# SerialLvlConvert.net
KiCad netlist of a schematic drawn in Altium Designer
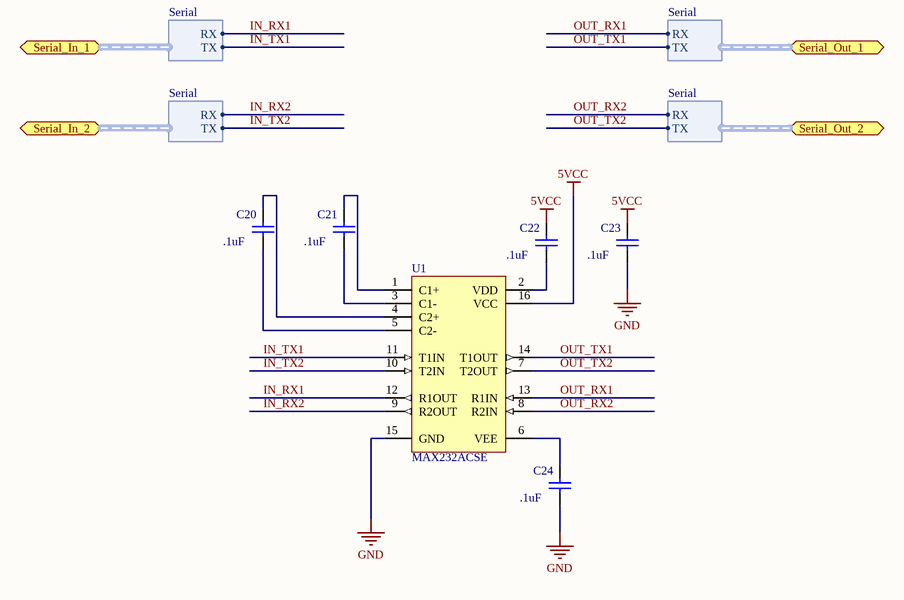
[diagram p0: SerialLvlConvert.SchDoc]

(export (version "E")
  (design (tool "Eeschema 10.0.6"))
  (components
    (comp (ref "C20")
      (value ".1uF")
      (footprint "0402")
      (description "Capacitor (Semiconductor SIM Model)")
      (fields (field (name "Comment") "Cap Semi") (field (name "PUBLISHER") "Altium Limited"))
      (libsource (lib "Miscellaneous Devices") (part "Cap Semi"))
    )
    (comp (ref "C21")
      (value ".1uF")
      (footprint "0402")
      (description "Capacitor (Semiconductor SIM Model)")
      (fields (field (name "Comment") "Cap Semi") (field (name "PUBLISHER") "Altium Limited"))
      (libsource (lib "Miscellaneous Devices") (part "Cap Semi"))
    )
    (comp (ref "C22")
      (value ".1uF")
      (footprint "0402")
      (description "Capacitor (Semiconductor SIM Model)")
      (fields (field (name "Comment") "Cap Semi") (field (name "PUBLISHER") "Altium Limited"))
      (libsource (lib "Miscellaneous Devices") (part "Cap Semi"))
    )
    (comp (ref "C23")
      (value ".1uF")
      (footprint "0402")
      (description "Capacitor (Semiconductor SIM Model)")
      (fields (field (name "Comment") "Cap Semi") (field (name "PUBLISHER") "Altium Limited"))
      (libsource (lib "Miscellaneous Devices") (part "Cap Semi"))
    )
    (comp (ref "C24")
      (value ".1uF")
      (footprint "0402")
      (description "Capacitor (Semiconductor SIM Model)")
      (fields (field (name "Comment") "Cap Semi") (field (name "PUBLISHER") "Altium Limited"))
      (libsource (lib "Miscellaneous Devices") (part "Cap Semi"))
    )
    (comp (ref "U1")
      (value "MAX232ACSE")
      (footprint "Maxim Footprints:NSO16_N")
      (description "+5V Powered, Multi-Channel RS-232 Driver/Receiver")
      (fields (field (name "PUBLISHER") "Altium Limited"))
      (libsource (lib "Maxim Communication Transceiver") (part "MAX232ACSE"))
    )
  )
  (nets
    (net (code "2") (name "/IN_RX1") (class "Default")
      (node (ref "U1") (pin "12") (pinfunction "R1OUT_12") (pintype "output"))
    )
    (net (code "3") (name "/IN_RX2") (class "Default")
      (node (ref "U1") (pin "9") (pinfunction "R2OUT_9") (pintype "output"))
    )
    (net (code "4") (name "/IN_TX1") (class "Default")
      (node (ref "U1") (pin "11") (pinfunction "T1IN_11") (pintype "input"))
    )
    (net (code "5") (name "/IN_TX2") (class "Default")
      (node (ref "U1") (pin "10") (pinfunction "T2IN_10") (pintype "input"))
    )
    (net (code "6") (name "/OUT_RX1") (class "Default")
      (node (ref "U1") (pin "13") (pinfunction "R1IN_13") (pintype "input"))
    )
    (net (code "7") (name "/OUT_RX2") (class "Default")
      (node (ref "U1") (pin "8") (pinfunction "R2IN_8") (pintype "input"))
    )
    (net (code "8") (name "/OUT_TX1") (class "Default")
      (node (ref "U1") (pin "14") (pinfunction "T1OUT_14") (pintype "output"))
    )
    (net (code "9") (name "/OUT_TX2") (class "Default")
      (node (ref "U1") (pin "7") (pinfunction "T2OUT_7") (pintype "output"))
    )
    (net (code "11") (name "5VCC") (class "Default")
      (node (ref "C22") (pin "1") (pinfunction "1_1") (pintype "passive"))
      (node (ref "C23") (pin "1") (pinfunction "1_1") (pintype "passive"))
      (node (ref "U1") (pin "16") (pinfunction "VCC_16") (pintype "power_in"))
    )
    (net (code "12") (name "GND") (class "Default")
      (node (ref "C23") (pin "2") (pinfunction "2_2") (pintype "passive"))
      (node (ref "C24") (pin "2") (pinfunction "2_2") (pintype "passive"))
      (node (ref "U1") (pin "15") (pinfunction "GND_15") (pintype "power_in"))
    )
    (net (code "13") (name "Net-(U1-C1+)") (class "Default")
      (node (ref "C21") (pin "1") (pinfunction "1_1") (pintype "passive"))
      (node (ref "U1") (pin "1") (pinfunction "C1+_1") (pintype "passive"))
    )
    (net (code "14") (name "Net-(U1-C1-)") (class "Default")
      (node (ref "C21") (pin "2") (pinfunction "2_2") (pintype "passive"))
      (node (ref "U1") (pin "3") (pinfunction "C1-_3") (pintype "passive"))
    )
    (net (code "15") (name "Net-(U1-C2+)") (class "Default")
      (node (ref "C20") (pin "1") (pinfunction "1_1") (pintype "passive"))
      (node (ref "U1") (pin "4") (pinfunction "C2+_4") (pintype "passive"))
    )
    (net (code "16") (name "Net-(U1-C2-)") (class "Default")
      (node (ref "C20") (pin "2") (pinfunction "2_2") (pintype "passive"))
      (node (ref "U1") (pin "5") (pinfunction "C2-_5") (pintype "passive"))
    )
    (net (code "17") (name "Net-(U1-VDD)") (class "Default")
      (node (ref "C22") (pin "2") (pinfunction "2_2") (pintype "passive"))
      (node (ref "U1") (pin "2") (pinfunction "VDD_2") (pintype "power_in"))
    )
    (net (code "18") (name "Net-(U1-VEE)") (class "Default")
      (node (ref "C24") (pin "1") (pinfunction "1_1") (pintype "passive"))
      (node (ref "U1") (pin "6") (pinfunction "VEE_6") (pintype "power_in"))
    )
  )
)
